# zumy_carrier_board.net
KiCad netlist of a schematic drawn in EAGLE
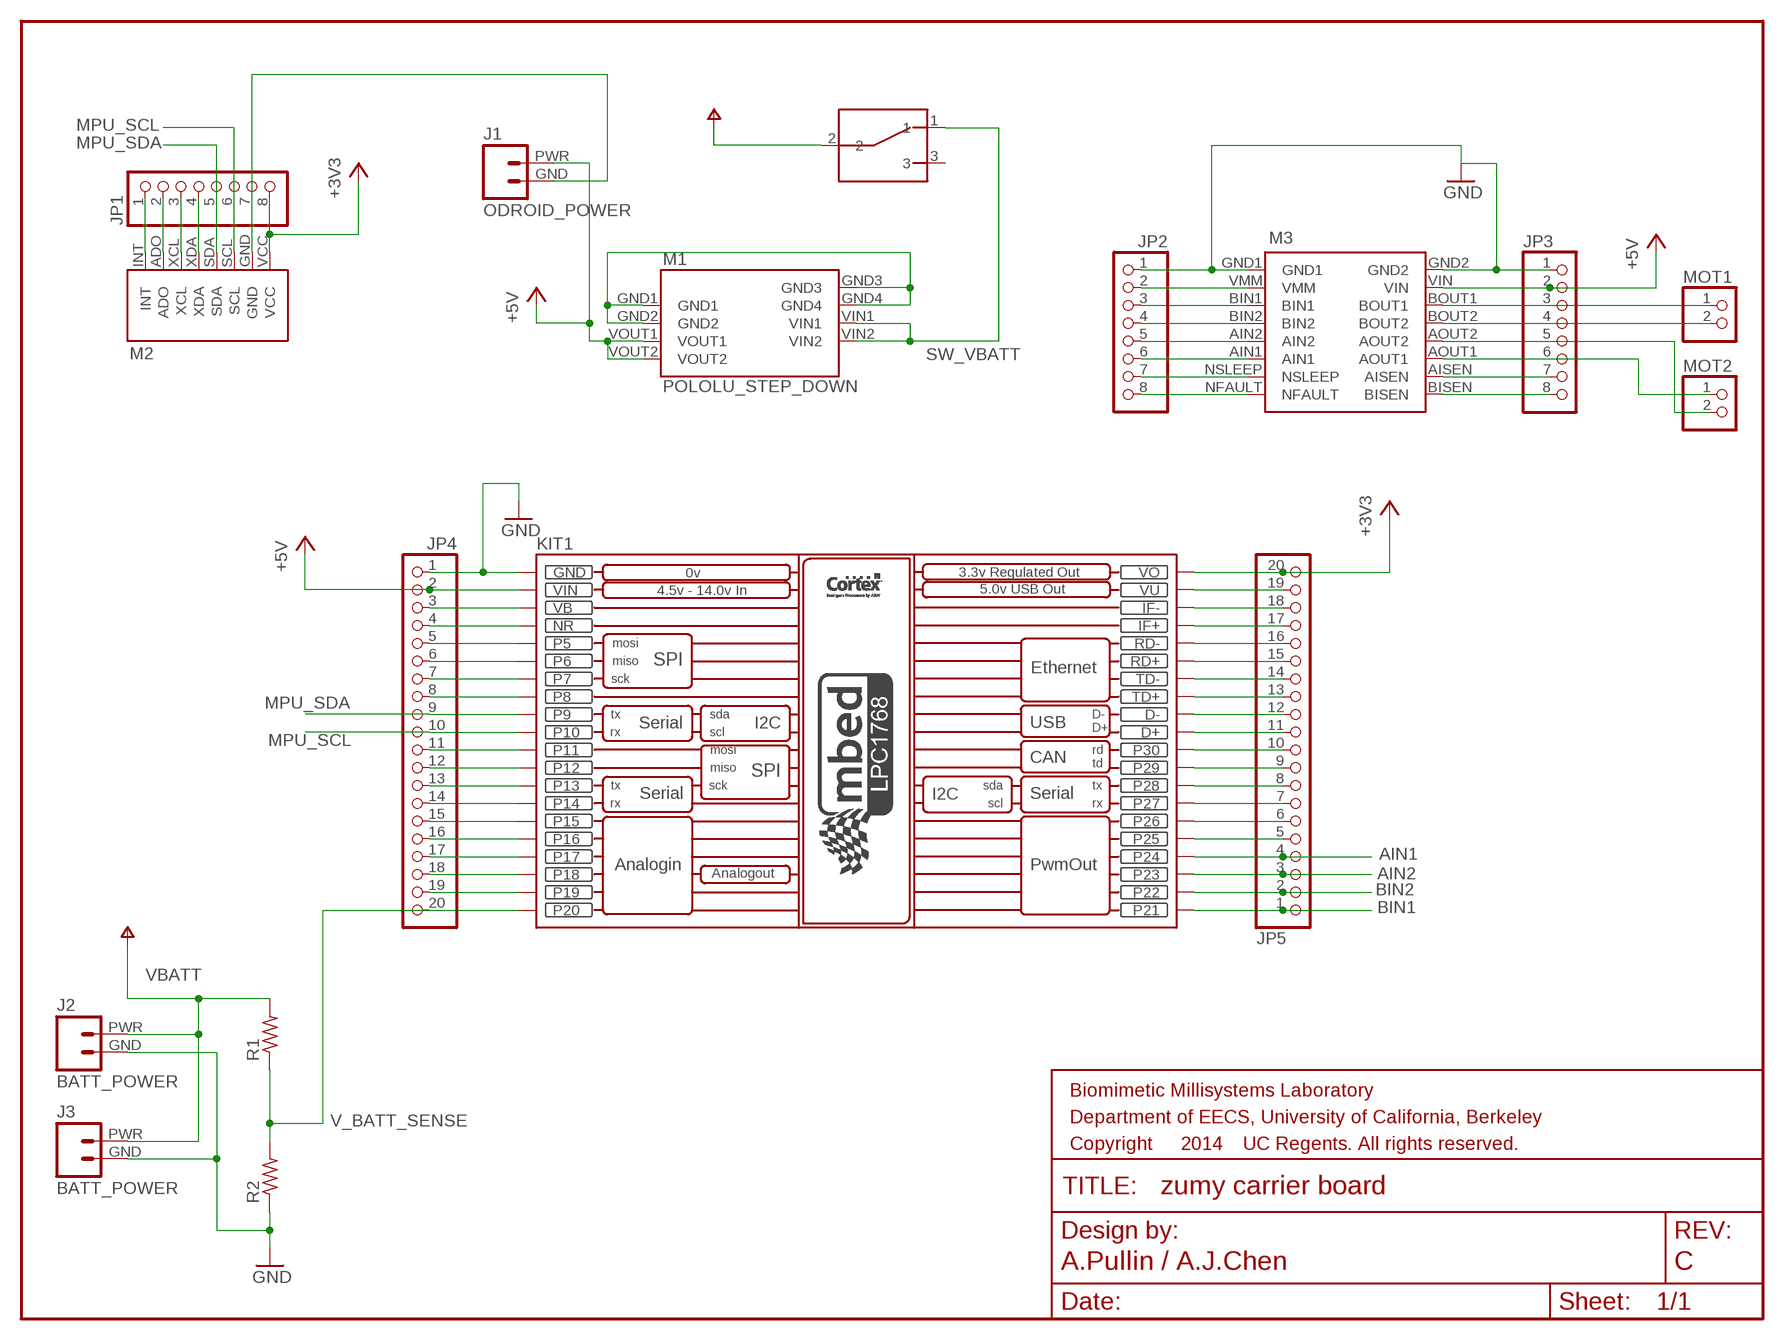
[diagram p0: schematic, sheet 1]

(export (version "E")
  (design (tool "Eeschema 10.0.6"))
  (components
    (comp (ref "J1")
      (value "ODROID_POWER")
      (footprint "eagle-import:ODOIRD_PWR")
      (libsource (lib "eagle-import") (part "ODROID_POWER"))
    )
    (comp (ref "J2")
      (value "BATT_POWER")
      (footprint "eagle-import:BATT_POWER")
      (libsource (lib "eagle-import") (part "BATT_POWER"))
    )
    (comp (ref "J3")
      (value "BATT_POWER")
      (footprint "eagle-import:BATT_POWER")
      (libsource (lib "eagle-import") (part "BATT_POWER"))
    )
    (comp (ref "JP1")
      (value "PINHD-1X8")
      (footprint "eagle-import:1X08")
      (libsource (lib "eagle-import") (part "PINHD-1X8"))
    )
    (comp (ref "JP2")
      (value "PINHD-1X8")
      (footprint "eagle-import:1X08")
      (libsource (lib "eagle-import") (part "PINHD-1X8"))
    )
    (comp (ref "JP3")
      (value "PINHD-1X8")
      (footprint "eagle-import:1X08")
      (libsource (lib "eagle-import") (part "PINHD-1X8"))
    )
    (comp (ref "JP4")
      (value "PINHD-1X20")
      (footprint "eagle-import:1X20")
      (libsource (lib "eagle-import") (part "PINHD-1X20"))
    )
    (comp (ref "JP5")
      (value "PINHD-1X20")
      (footprint "eagle-import:1X20")
      (libsource (lib "eagle-import") (part "PINHD-1X20"))
    )
    (comp (ref "KIT1")
      (value "MBED_NXP_LPC1768")
      (footprint "eagle-import:MBED-KIT")
      (libsource (lib "eagle-import") (part "MBED_NXP_LPC1768"))
    )
    (comp (ref "M1")
      (value "POLOLU_STEP_DOWN")
      (footprint "eagle-import:POLOLU_STEP_DOWN")
      (libsource (lib "eagle-import") (part "POLOLU_STEP_DOWN"))
    )
    (comp (ref "M2")
      (value "ITG/MPU_MODULE")
      (footprint "eagle-import:ITG_MPU_MODULE")
      (libsource (lib "eagle-import") (part "ITG/MPU_MODULE"))
    )
    (comp (ref "M3")
      (value "POLOLU_DRV8833_MODULE")
      (footprint "eagle-import:POLOLU_DRV8833_MODULE")
      (libsource (lib "eagle-import") (part "POLOLU_DRV8833_MODULE"))
    )
    (comp (ref "MOT1")
      (value "PINHD-1X2")
      (footprint "eagle-import:1X02")
      (libsource (lib "eagle-import") (part "PINHD-1X2"))
    )
    (comp (ref "MOT2")
      (value "PINHD-1X2")
      (footprint "eagle-import:1X02")
      (libsource (lib "eagle-import") (part "PINHD-1X2"))
    )
    (comp (ref "R1")
      (value "R-US_0204/5")
      (footprint "eagle-import:0204_5")
      (libsource (lib "eagle-import") (part "R-US_0204/5"))
    )
    (comp (ref "R2")
      (value "R-US_0204/5")
      (footprint "eagle-import:0204_5")
      (libsource (lib "eagle-import") (part "R-US_0204/5"))
    )
    (comp (ref "SW1")
      (value "500SSP1S1M6QEA")
      (footprint "eagle-import:500SSP1S1M6QEA_SWITCH")
      (libsource (lib "eagle-import") (part "500SSP1S1M6QEA"))
    )
  )
  (nets
    (net (code "1") (name "+3V3") (class "Default")
      (node (ref "JP1") (pin "8") (pinfunction "8_8") (pintype "passive"))
      (node (ref "JP5") (pin "20") (pinfunction "20_20") (pintype "passive"))
      (node (ref "KIT1") (pin "VOUT") (pinfunction "VO_VOUT") (pintype "power_in"))
      (node (ref "M2") (pin "VCC") (pinfunction "VCC_VCC") (pintype "bidirectional"))
    )
    (net (code "2") (name "+5V") (class "Default")
      (node (ref "J1") (pin "PWR") (pinfunction "PWR_PWR") (pintype "passive"))
      (node (ref "JP3") (pin "2") (pinfunction "2_2") (pintype "passive"))
      (node (ref "JP4") (pin "2") (pinfunction "2_2") (pintype "passive"))
      (node (ref "KIT1") (pin "VIN") (pinfunction "VIN_VIN") (pintype "power_in"))
      (node (ref "M1") (pin "VOUT1") (pinfunction "VOUT1_VOUT1") (pintype "bidirectional"))
      (node (ref "M1") (pin "VOUT2") (pinfunction "VOUT2_VOUT2") (pintype "bidirectional"))
      (node (ref "M3") (pin "VIN") (pinfunction "VIN_VIN") (pintype "bidirectional"))
    )
    (net (code "3") (name "/AIN1") (class "Default")
      (node (ref "JP2") (pin "6") (pinfunction "6_6") (pintype "passive"))
      (node (ref "JP5") (pin "4") (pinfunction "4_4") (pintype "passive"))
      (node (ref "KIT1") (pin "P$24") (pinfunction "P24_P$24") (pintype "bidirectional"))
      (node (ref "M3") (pin "AIN1") (pinfunction "AIN1_AIN1") (pintype "bidirectional"))
    )
    (net (code "4") (name "/AIN2") (class "Default")
      (node (ref "JP2") (pin "5") (pinfunction "5_5") (pintype "passive"))
      (node (ref "JP5") (pin "3") (pinfunction "3_3") (pintype "passive"))
      (node (ref "KIT1") (pin "P$23") (pinfunction "P23_P$23") (pintype "bidirectional"))
      (node (ref "M3") (pin "AIN2") (pinfunction "AIN2_AIN2") (pintype "bidirectional"))
    )
    (net (code "5") (name "/BIN1") (class "Default")
      (node (ref "JP2") (pin "3") (pinfunction "3_3") (pintype "passive"))
      (node (ref "JP5") (pin "1") (pinfunction "1_1") (pintype "passive"))
      (node (ref "KIT1") (pin "P$21") (pinfunction "P21_P$21") (pintype "bidirectional"))
      (node (ref "M3") (pin "BIN1") (pinfunction "BIN1_BIN1") (pintype "bidirectional"))
    )
    (net (code "6") (name "/BIN2") (class "Default")
      (node (ref "JP2") (pin "4") (pinfunction "4_4") (pintype "passive"))
      (node (ref "JP5") (pin "2") (pinfunction "2_2") (pintype "passive"))
      (node (ref "KIT1") (pin "P$22") (pinfunction "P22_P$22") (pintype "bidirectional"))
      (node (ref "M3") (pin "BIN2") (pinfunction "BIN2_BIN2") (pintype "bidirectional"))
    )
    (net (code "7") (name "/MPU_SCL") (class "Default")
      (node (ref "JP1") (pin "6") (pinfunction "6_6") (pintype "passive"))
      (node (ref "JP4") (pin "10") (pinfunction "10_10") (pintype "passive"))
      (node (ref "KIT1") (pin "P$10") (pinfunction "P10_P$10") (pintype "bidirectional"))
      (node (ref "M2") (pin "SCL") (pinfunction "SCL_SCL") (pintype "bidirectional"))
    )
    (net (code "8") (name "/MPU_SDA") (class "Default")
      (node (ref "JP1") (pin "5") (pinfunction "5_5") (pintype "passive"))
      (node (ref "JP4") (pin "9") (pinfunction "9_9") (pintype "passive"))
      (node (ref "KIT1") (pin "P$9") (pinfunction "P9_P$9") (pintype "bidirectional"))
      (node (ref "M2") (pin "SDA") (pinfunction "SDA_SDA") (pintype "bidirectional"))
    )
    (net (code "9") (name "/SW_VBATT") (class "Default")
      (node (ref "M1") (pin "VIN1") (pinfunction "VIN1_VIN1") (pintype "bidirectional"))
      (node (ref "M1") (pin "VIN2") (pinfunction "VIN2_VIN2") (pintype "bidirectional"))
      (node (ref "SW1") (pin "1") (pinfunction "1_1") (pintype "bidirectional"))
    )
    (net (code "10") (name "/V_BATT_SENSE") (class "Default")
      (node (ref "JP4") (pin "20") (pinfunction "20_20") (pintype "passive"))
      (node (ref "KIT1") (pin "P$20") (pinfunction "P20_P$20") (pintype "bidirectional"))
      (node (ref "R1") (pin "1") (pinfunction "1_1") (pintype "passive"))
      (node (ref "R2") (pin "2") (pinfunction "2_2") (pintype "passive"))
    )
    (net (code "11") (name "GND") (class "Default")
      (node (ref "J2") (pin "GND") (pinfunction "GND_GND") (pintype "passive"))
      (node (ref "J3") (pin "GND") (pinfunction "GND_GND") (pintype "passive"))
      (node (ref "JP2") (pin "1") (pinfunction "1_1") (pintype "passive"))
      (node (ref "JP3") (pin "1") (pinfunction "1_1") (pintype "passive"))
      (node (ref "JP4") (pin "1") (pinfunction "1_1") (pintype "passive"))
      (node (ref "KIT1") (pin "GND") (pinfunction "GND_GND") (pintype "power_in"))
      (node (ref "M3") (pin "GND1") (pinfunction "GND1_GND1") (pintype "bidirectional"))
      (node (ref "M3") (pin "GND2") (pinfunction "GND2_GND2") (pintype "bidirectional"))
      (node (ref "R2") (pin "1") (pinfunction "1_1") (pintype "passive"))
    )
    (net (code "12") (name "Net-(J1-PadGND)") (class "Default")
      (node (ref "J1") (pin "GND") (pinfunction "GND_GND") (pintype "passive"))
      (node (ref "JP1") (pin "7") (pinfunction "7_7") (pintype "passive"))
      (node (ref "M2") (pin "GND") (pinfunction "GND_GND") (pintype "bidirectional"))
    )
    (net (code "13") (name "Net-(JP1-Pad1)") (class "Default")
      (node (ref "JP1") (pin "1") (pinfunction "1_1") (pintype "passive"))
      (node (ref "M2") (pin "INT") (pinfunction "INT_INT") (pintype "bidirectional"))
    )
    (net (code "14") (name "Net-(JP1-Pad2)") (class "Default")
      (node (ref "JP1") (pin "2") (pinfunction "2_2") (pintype "passive"))
      (node (ref "M2") (pin "ADO") (pinfunction "ADO_ADO") (pintype "bidirectional"))
    )
    (net (code "15") (name "Net-(JP1-Pad3)") (class "Default")
      (node (ref "JP1") (pin "3") (pinfunction "3_3") (pintype "passive"))
      (node (ref "M2") (pin "XCL") (pinfunction "XCL_XCL") (pintype "bidirectional"))
    )
    (net (code "16") (name "Net-(JP1-Pad4)") (class "Default")
      (node (ref "JP1") (pin "4") (pinfunction "4_4") (pintype "passive"))
      (node (ref "M2") (pin "XDA") (pinfunction "XDA_XDA") (pintype "bidirectional"))
    )
    (net (code "17") (name "Net-(JP2-Pad2)") (class "Default")
      (node (ref "JP2") (pin "2") (pinfunction "2_2") (pintype "passive"))
      (node (ref "M3") (pin "VMM") (pinfunction "VMM_VMM") (pintype "bidirectional"))
    )
    (net (code "18") (name "Net-(JP2-Pad7)") (class "Default")
      (node (ref "JP2") (pin "7") (pinfunction "7_7") (pintype "passive"))
      (node (ref "M3") (pin "NSLEEP") (pinfunction "NSLEEP_NSLEEP") (pintype "bidirectional"))
    )
    (net (code "19") (name "Net-(JP2-Pad8)") (class "Default")
      (node (ref "JP2") (pin "8") (pinfunction "8_8") (pintype "passive"))
      (node (ref "M3") (pin "NFAULT") (pinfunction "NFAULT_NFAULT") (pintype "bidirectional"))
    )
    (net (code "20") (name "Net-(JP3-Pad3)") (class "Default")
      (node (ref "JP3") (pin "3") (pinfunction "3_3") (pintype "passive"))
      (node (ref "M3") (pin "BOUT1") (pinfunction "BOUT1_BOUT1") (pintype "bidirectional"))
      (node (ref "MOT1") (pin "1") (pinfunction "1_1") (pintype "passive"))
    )
    (net (code "21") (name "Net-(JP3-Pad4)") (class "Default")
      (node (ref "JP3") (pin "4") (pinfunction "4_4") (pintype "passive"))
      (node (ref "M3") (pin "BOUT2") (pinfunction "BOUT2_BOUT2") (pintype "bidirectional"))
      (node (ref "MOT1") (pin "2") (pinfunction "2_2") (pintype "passive"))
    )
    (net (code "22") (name "Net-(JP3-Pad5)") (class "Default")
      (node (ref "JP3") (pin "5") (pinfunction "5_5") (pintype "passive"))
      (node (ref "M3") (pin "AOUT2") (pinfunction "AOUT2_AOUT2") (pintype "bidirectional"))
      (node (ref "MOT2") (pin "2") (pinfunction "2_2") (pintype "passive"))
    )
    (net (code "23") (name "Net-(JP3-Pad6)") (class "Default")
      (node (ref "JP3") (pin "6") (pinfunction "6_6") (pintype "passive"))
      (node (ref "M3") (pin "AOUT1") (pinfunction "AOUT1_AOUT1") (pintype "bidirectional"))
      (node (ref "MOT2") (pin "1") (pinfunction "1_1") (pintype "passive"))
    )
    (net (code "24") (name "Net-(JP3-Pad7)") (class "Default")
      (node (ref "JP3") (pin "7") (pinfunction "7_7") (pintype "passive"))
      (node (ref "M3") (pin "AISEN") (pinfunction "AISEN_AISEN") (pintype "bidirectional"))
    )
    (net (code "25") (name "Net-(JP3-Pad8)") (class "Default")
      (node (ref "JP3") (pin "8") (pinfunction "8_8") (pintype "passive"))
      (node (ref "M3") (pin "BISEN") (pinfunction "BISEN_BISEN") (pintype "bidirectional"))
    )
    (net (code "26") (name "Net-(JP4-Pad3)") (class "Default")
      (node (ref "JP4") (pin "3") (pinfunction "3_3") (pintype "passive"))
      (node (ref "KIT1") (pin "VB") (pinfunction "VB_VB") (pintype "power_in"))
    )
    (net (code "27") (name "Net-(JP4-Pad4)") (class "Default")
      (node (ref "JP4") (pin "4") (pinfunction "4_4") (pintype "passive"))
      (node (ref "KIT1") (pin "NR") (pinfunction "NR_NR") (pintype "power_in"))
    )
    (net (code "28") (name "Net-(JP5-Pad11)") (class "Default")
      (node (ref "JP5") (pin "11") (pinfunction "11_11") (pintype "passive"))
      (node (ref "KIT1") (pin "D+") (pinfunction "D+_D+") (pintype "bidirectional"))
    )
    (net (code "29") (name "Net-(JP5-Pad12)") (class "Default")
      (node (ref "JP5") (pin "12") (pinfunction "12_12") (pintype "passive"))
      (node (ref "KIT1") (pin "D-") (pinfunction "D-_D-") (pintype "bidirectional"))
    )
    (net (code "30") (name "Net-(JP5-Pad13)") (class "Default")
      (node (ref "JP5") (pin "13") (pinfunction "13_13") (pintype "passive"))
      (node (ref "KIT1") (pin "TD+") (pinfunction "TD+_TD+") (pintype "bidirectional"))
    )
    (net (code "31") (name "Net-(JP5-Pad14)") (class "Default")
      (node (ref "JP5") (pin "14") (pinfunction "14_14") (pintype "passive"))
      (node (ref "KIT1") (pin "TD-") (pinfunction "TD-_TD-") (pintype "bidirectional"))
    )
    (net (code "32") (name "Net-(JP5-Pad15)") (class "Default")
      (node (ref "JP5") (pin "15") (pinfunction "15_15") (pintype "passive"))
      (node (ref "KIT1") (pin "RD+") (pinfunction "RD+_RD+") (pintype "bidirectional"))
    )
    (net (code "33") (name "Net-(JP5-Pad16)") (class "Default")
      (node (ref "JP5") (pin "16") (pinfunction "16_16") (pintype "passive"))
      (node (ref "KIT1") (pin "RD-") (pinfunction "RD-_RD-") (pintype "bidirectional"))
    )
    (net (code "34") (name "Net-(JP5-Pad17)") (class "Default")
      (node (ref "JP5") (pin "17") (pinfunction "17_17") (pintype "passive"))
      (node (ref "KIT1") (pin "IF+") (pinfunction "IF+_IF+") (pintype "bidirectional"))
    )
    (net (code "35") (name "Net-(JP5-Pad18)") (class "Default")
      (node (ref "JP5") (pin "18") (pinfunction "18_18") (pintype "passive"))
      (node (ref "KIT1") (pin "IF-") (pinfunction "IF-_IF-") (pintype "bidirectional"))
    )
    (net (code "36") (name "Net-(JP5-Pad19)") (class "Default")
      (node (ref "JP5") (pin "19") (pinfunction "19_19") (pintype "passive"))
      (node (ref "KIT1") (pin "VU") (pinfunction "VU_VU") (pintype "power_in"))
    )
    (net (code "37") (name "Net-(KIT1-P5)") (class "Default")
      (node (ref "JP4") (pin "5") (pinfunction "5_5") (pintype "passive"))
      (node (ref "KIT1") (pin "P$5") (pinfunction "P5_P$5") (pintype "bidirectional"))
    )
    (net (code "38") (name "Net-(KIT1-P6)") (class "Default")
      (node (ref "JP4") (pin "6") (pinfunction "6_6") (pintype "passive"))
      (node (ref "KIT1") (pin "P$6") (pinfunction "P6_P$6") (pintype "bidirectional"))
    )
    (net (code "39") (name "Net-(KIT1-P7)") (class "Default")
      (node (ref "JP4") (pin "7") (pinfunction "7_7") (pintype "passive"))
      (node (ref "KIT1") (pin "P$7") (pinfunction "P7_P$7") (pintype "bidirectional"))
    )
    (net (code "40") (name "Net-(KIT1-P8)") (class "Default")
      (node (ref "JP4") (pin "8") (pinfunction "8_8") (pintype "passive"))
      (node (ref "KIT1") (pin "P$8") (pinfunction "P8_P$8") (pintype "bidirectional"))
    )
    (net (code "41") (name "Net-(KIT1-P11)") (class "Default")
      (node (ref "JP4") (pin "11") (pinfunction "11_11") (pintype "passive"))
      (node (ref "KIT1") (pin "P$11") (pinfunction "P11_P$11") (pintype "bidirectional"))
    )
    (net (code "42") (name "Net-(KIT1-P12)") (class "Default")
      (node (ref "JP4") (pin "12") (pinfunction "12_12") (pintype "passive"))
      (node (ref "KIT1") (pin "P$12") (pinfunction "P12_P$12") (pintype "bidirectional"))
    )
    (net (code "43") (name "Net-(KIT1-P13)") (class "Default")
      (node (ref "JP4") (pin "13") (pinfunction "13_13") (pintype "passive"))
      (node (ref "KIT1") (pin "P$13") (pinfunction "P13_P$13") (pintype "bidirectional"))
    )
    (net (code "44") (name "Net-(KIT1-P14)") (class "Default")
      (node (ref "JP4") (pin "14") (pinfunction "14_14") (pintype "passive"))
      (node (ref "KIT1") (pin "P$14") (pinfunction "P14_P$14") (pintype "bidirectional"))
    )
    (net (code "45") (name "Net-(KIT1-P15)") (class "Default")
      (node (ref "JP4") (pin "15") (pinfunction "15_15") (pintype "passive"))
      (node (ref "KIT1") (pin "P$15") (pinfunction "P15_P$15") (pintype "bidirectional"))
    )
    (net (code "46") (name "Net-(KIT1-P16)") (class "Default")
      (node (ref "JP4") (pin "16") (pinfunction "16_16") (pintype "passive"))
      (node (ref "KIT1") (pin "P$16") (pinfunction "P16_P$16") (pintype "bidirectional"))
    )
    (net (code "47") (name "Net-(KIT1-P17)") (class "Default")
      (node (ref "JP4") (pin "17") (pinfunction "17_17") (pintype "passive"))
      (node (ref "KIT1") (pin "P$17") (pinfunction "P17_P$17") (pintype "bidirectional"))
    )
    (net (code "48") (name "Net-(KIT1-P18)") (class "Default")
      (node (ref "JP4") (pin "18") (pinfunction "18_18") (pintype "passive"))
      (node (ref "KIT1") (pin "P$18") (pinfunction "P18_P$18") (pintype "bidirectional"))
    )
    (net (code "49") (name "Net-(KIT1-P19)") (class "Default")
      (node (ref "JP4") (pin "19") (pinfunction "19_19") (pintype "passive"))
      (node (ref "KIT1") (pin "P$19") (pinfunction "P19_P$19") (pintype "bidirectional"))
    )
    (net (code "50") (name "Net-(KIT1-P25)") (class "Default")
      (node (ref "JP5") (pin "5") (pinfunction "5_5") (pintype "passive"))
      (node (ref "KIT1") (pin "P$25") (pinfunction "P25_P$25") (pintype "bidirectional"))
    )
    (net (code "51") (name "Net-(KIT1-P26)") (class "Default")
      (node (ref "JP5") (pin "6") (pinfunction "6_6") (pintype "passive"))
      (node (ref "KIT1") (pin "P$26") (pinfunction "P26_P$26") (pintype "bidirectional"))
    )
    (net (code "52") (name "Net-(KIT1-P27)") (class "Default")
      (node (ref "JP5") (pin "7") (pinfunction "7_7") (pintype "passive"))
      (node (ref "KIT1") (pin "P$27") (pinfunction "P27_P$27") (pintype "bidirectional"))
    )
    (net (code "53") (name "Net-(KIT1-P28)") (class "Default")
      (node (ref "JP5") (pin "8") (pinfunction "8_8") (pintype "passive"))
      (node (ref "KIT1") (pin "P$28") (pinfunction "P28_P$28") (pintype "bidirectional"))
    )
    (net (code "54") (name "Net-(KIT1-P29)") (class "Default")
      (node (ref "JP5") (pin "9") (pinfunction "9_9") (pintype "passive"))
      (node (ref "KIT1") (pin "P$29") (pinfunction "P29_P$29") (pintype "bidirectional"))
    )
    (net (code "55") (name "Net-(KIT1-P30)") (class "Default")
      (node (ref "JP5") (pin "10") (pinfunction "10_10") (pintype "passive"))
      (node (ref "KIT1") (pin "P$30") (pinfunction "P30_P$30") (pintype "bidirectional"))
    )
    (net (code "56") (name "Net-(M1-PadGND1)") (class "Default")
      (node (ref "M1") (pin "GND1") (pinfunction "GND1_GND1") (pintype "bidirectional"))
      (node (ref "M1") (pin "GND2") (pinfunction "GND2_GND2") (pintype "bidirectional"))
      (node (ref "M1") (pin "GND3") (pinfunction "GND3_GND3") (pintype "bidirectional"))
      (node (ref "M1") (pin "GND4") (pinfunction "GND4_GND4") (pintype "bidirectional"))
    )
    (net (code "57") (name "V+") (class "Default")
      (node (ref "J2") (pin "PWR") (pinfunction "PWR_PWR") (pintype "passive"))
      (node (ref "J3") (pin "PWR") (pinfunction "PWR_PWR") (pintype "passive"))
      (node (ref "R1") (pin "2") (pinfunction "2_2") (pintype "passive"))
      (node (ref "SW1") (pin "2") (pinfunction "2_2") (pintype "bidirectional"))
    )
    (net (code "58") (name "unconnected-(SW1-Pad3)") (class "Default")
      (node (ref "SW1") (pin "3") (pinfunction "3_3") (pintype "bidirectional"))
    )
  )
)
